# programmer.net
KiCad netlist of a schematic drawn in EAGLE
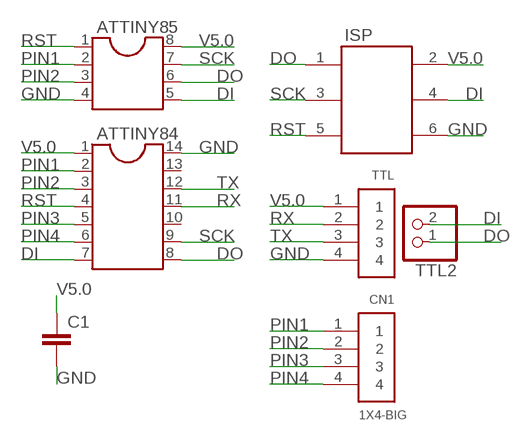
[diagram p0: schematic, sheet 1]

(export (version "E")
  (design (tool "Eeschema 10.0.6"))
  (components
    (comp (ref "ATTINY84")
      (value "DIL14S")
      (footprint "eagle-import:SOCKET-14")
      (libsource (lib "eagle-import") (part "DIL14S"))
    )
    (comp (ref "ATTINY85")
      (value "DIL8S")
      (footprint "eagle-import:SOCKET-08")
      (libsource (lib "eagle-import") (part "DIL8S"))
    )
    (comp (ref "C1")
      (value "C-EU025-025X050")
      (footprint "eagle-import:C025-025X050")
      (libsource (lib "eagle-import") (part "C-EU025-025X050"))
    )
    (comp (ref "CN1")
      (value "1X4-BIG")
      (footprint "eagle-import:1X04-BIG")
      (libsource (lib "eagle-import") (part "1X4-BIG"))
    )
    (comp (ref "ISP")
      (value "61200621621")
      (footprint "eagle-import:61200621621")
      (libsource (lib "eagle-import") (part "61200621621"))
    )
    (comp (ref "TTL")
      (value "1X4-BIG")
      (footprint "eagle-import:1X04-BIG")
      (libsource (lib "eagle-import") (part "1X4-BIG"))
    )
    (comp (ref "TTL2")
      (value "PINHD-1X2")
      (footprint "eagle-import:1X02")
      (libsource (lib "eagle-import") (part "PINHD-1X2"))
    )
  )
  (nets
    (net (code "1") (name "/DI") (class "Default")
      (node (ref "ATTINY84") (pin "7") (pinfunction "7_7") (pintype "passive"))
      (node (ref "ATTINY85") (pin "5") (pinfunction "5_5") (pintype "passive"))
      (node (ref "ISP") (pin "4") (pinfunction "4_4") (pintype "passive"))
      (node (ref "TTL2") (pin "2") (pinfunction "2_2") (pintype "passive"))
    )
    (net (code "2") (name "/DO") (class "Default")
      (node (ref "ATTINY84") (pin "8") (pinfunction "8_8") (pintype "passive"))
      (node (ref "ATTINY85") (pin "6") (pinfunction "6_6") (pintype "passive"))
      (node (ref "ISP") (pin "1") (pinfunction "1_1") (pintype "passive"))
      (node (ref "TTL2") (pin "1") (pinfunction "1_1") (pintype "passive"))
    )
    (net (code "3") (name "/GND") (class "Default")
      (node (ref "ATTINY84") (pin "14") (pinfunction "14_14") (pintype "passive"))
      (node (ref "ATTINY85") (pin "4") (pinfunction "4_4") (pintype "passive"))
      (node (ref "C1") (pin "2") (pinfunction "2_2") (pintype "passive"))
      (node (ref "ISP") (pin "6") (pinfunction "6_6") (pintype "passive"))
      (node (ref "TTL") (pin "4") (pinfunction "4_4") (pintype "bidirectional"))
    )
    (net (code "4") (name "/PIN1") (class "Default")
      (node (ref "ATTINY84") (pin "2") (pinfunction "2_2") (pintype "passive"))
      (node (ref "ATTINY85") (pin "2") (pinfunction "2_2") (pintype "passive"))
      (node (ref "CN1") (pin "1") (pinfunction "1_1") (pintype "bidirectional"))
    )
    (net (code "5") (name "/PIN2") (class "Default")
      (node (ref "ATTINY84") (pin "3") (pinfunction "3_3") (pintype "passive"))
      (node (ref "ATTINY85") (pin "3") (pinfunction "3_3") (pintype "passive"))
      (node (ref "CN1") (pin "2") (pinfunction "2_2") (pintype "bidirectional"))
    )
    (net (code "6") (name "/PIN3") (class "Default")
      (node (ref "ATTINY84") (pin "5") (pinfunction "5_5") (pintype "passive"))
      (node (ref "CN1") (pin "3") (pinfunction "3_3") (pintype "bidirectional"))
    )
    (net (code "7") (name "/PIN4") (class "Default")
      (node (ref "ATTINY84") (pin "6") (pinfunction "6_6") (pintype "passive"))
      (node (ref "CN1") (pin "4") (pinfunction "4_4") (pintype "bidirectional"))
    )
    (net (code "8") (name "/RST") (class "Default")
      (node (ref "ATTINY84") (pin "4") (pinfunction "4_4") (pintype "passive"))
      (node (ref "ATTINY85") (pin "1") (pinfunction "1_1") (pintype "passive"))
      (node (ref "ISP") (pin "5") (pinfunction "5_5") (pintype "passive"))
    )
    (net (code "9") (name "/RX") (class "Default")
      (node (ref "ATTINY84") (pin "11") (pinfunction "11_11") (pintype "passive"))
      (node (ref "TTL") (pin "2") (pinfunction "2_2") (pintype "bidirectional"))
    )
    (net (code "10") (name "/SCK") (class "Default")
      (node (ref "ATTINY84") (pin "9") (pinfunction "9_9") (pintype "passive"))
      (node (ref "ATTINY85") (pin "7") (pinfunction "7_7") (pintype "passive"))
      (node (ref "ISP") (pin "3") (pinfunction "3_3") (pintype "passive"))
    )
    (net (code "11") (name "/TX") (class "Default")
      (node (ref "ATTINY84") (pin "12") (pinfunction "12_12") (pintype "passive"))
      (node (ref "TTL") (pin "3") (pinfunction "3_3") (pintype "bidirectional"))
    )
    (net (code "12") (name "/V5.0") (class "Default")
      (node (ref "ATTINY84") (pin "1") (pinfunction "1_1") (pintype "passive"))
      (node (ref "ATTINY85") (pin "8") (pinfunction "8_8") (pintype "passive"))
      (node (ref "C1") (pin "1") (pinfunction "1_1") (pintype "passive"))
      (node (ref "ISP") (pin "2") (pinfunction "2_2") (pintype "passive"))
      (node (ref "TTL") (pin "1") (pinfunction "1_1") (pintype "bidirectional"))
    )
    (net (code "13") (name "unconnected-(ATTINY84-Pad10)") (class "Default")
      (node (ref "ATTINY84") (pin "10") (pinfunction "10_10") (pintype "passive"))
    )
    (net (code "14") (name "unconnected-(ATTINY84-Pad13)") (class "Default")
      (node (ref "ATTINY84") (pin "13") (pinfunction "13_13") (pintype "passive"))
    )
  )
)
